# MicroLipoV1_1.net
KiCad netlist of a schematic drawn in EAGLE
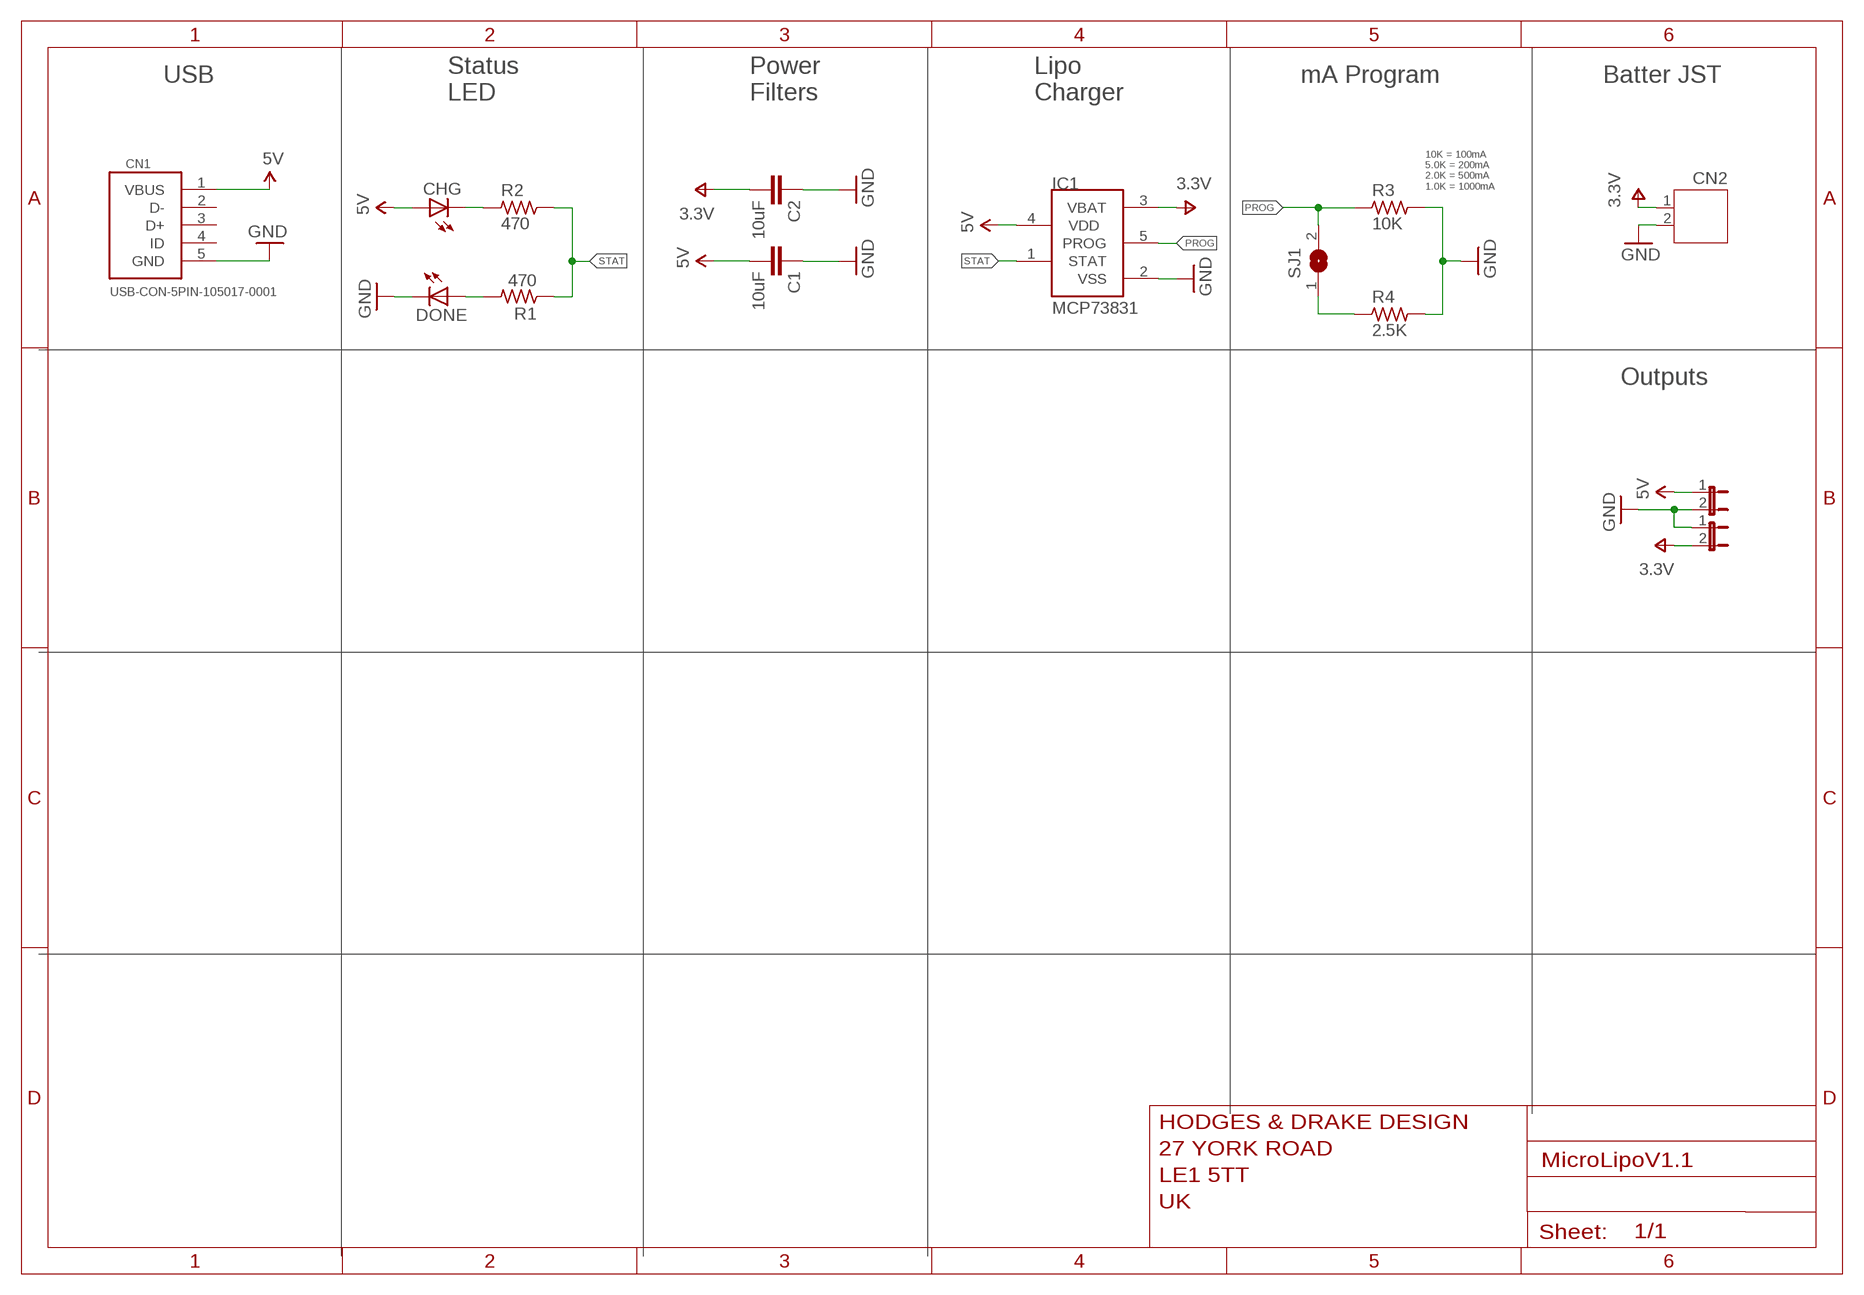
[diagram p0: schematic, sheet 1]

(export (version "E")
  (design (tool "Eeschema 10.0.6"))
  (components
    (comp (ref "C1")
      (value "10uF")
      (footprint "eagle-import:C0805K")
      (libsource (lib "eagle-import") (part "C-EUC0805K"))
    )
    (comp (ref "C2")
      (value "10uF")
      (footprint "eagle-import:C0805K")
      (libsource (lib "eagle-import") (part "C-EUC0805K"))
    )
    (comp (ref "CHG")
      (value "LEDCHIPLED_0805")
      (footprint "eagle-import:CHIPLED_0805")
      (libsource (lib "eagle-import") (part "LEDCHIPLED_0805"))
    )
    (comp (ref "CN1")
      (value "USB-CON-5PIN-105017-0001")
      (footprint "eagle-import:USB-MICRO-MOLEX-105017-0001")
      (libsource (lib "eagle-import") (part "USB-CON-5PIN-105017-0001"))
    )
    (comp (ref "CN2")
      (value "JST-PH2")
      (footprint "eagle-import:JST-PH2-S2B")
      (libsource (lib "eagle-import") (part "JST-PH2"))
    )
    (comp (ref "DONE")
      (value "LEDCHIPLED_0805")
      (footprint "eagle-import:CHIPLED_0805")
      (libsource (lib "eagle-import") (part "LEDCHIPLED_0805"))
    )
    (comp (ref "IC1")
      (value "MCP73831")
      (footprint "eagle-import:SOT23-5L")
      (libsource (lib "eagle-import") (part "MCP73831"))
    )
    (comp (ref "JP2")
      (value "JUMPER-2PTH")
      (footprint "eagle-import:1X02")
      (libsource (lib "eagle-import") (part "JUMPER-2PTH"))
    )
    (comp (ref "JP3")
      (value "JUMPER-2PTH")
      (footprint "eagle-import:1X02")
      (libsource (lib "eagle-import") (part "JUMPER-2PTH"))
    )
    (comp (ref "R1")
      (value "470")
      (footprint "eagle-import:R0805")
      (libsource (lib "eagle-import") (part "R_0805"))
    )
    (comp (ref "R2")
      (value "470")
      (footprint "eagle-import:R0805")
      (libsource (lib "eagle-import") (part "R_0805"))
    )
    (comp (ref "R3")
      (value "10K")
      (footprint "eagle-import:R0805")
      (libsource (lib "eagle-import") (part "R_0805"))
    )
    (comp (ref "R4")
      (value "2.5K")
      (footprint "eagle-import:R0805")
      (libsource (lib "eagle-import") (part "R_0805"))
    )
    (comp (ref "SJ1") (value "SJ") (footprint "eagle-import:SJ") (libsource (lib "eagle-import") (part "SJ")))
  )
  (nets
    (net (code "1") (name "3.3V") (class "Default")
      (node (ref "C2") (pin "2") (pinfunction "2_2") (pintype "passive"))
      (node (ref "CN2") (pin "1") (pinfunction "1_1") (pintype "passive"))
      (node (ref "IC1") (pin "3") (pinfunction "VBAT_3") (pintype "bidirectional"))
      (node (ref "JP3") (pin "2") (pinfunction "2_2") (pintype "passive"))
    )
    (net (code "2") (name "5V") (class "Default")
      (node (ref "C1") (pin "2") (pinfunction "2_2") (pintype "passive"))
      (node (ref "CHG") (pin "A") (pinfunction "A_A") (pintype "passive"))
      (node (ref "CN1") (pin "1") (pinfunction "VBUS_1") (pintype "power_in"))
      (node (ref "IC1") (pin "4") (pinfunction "VDD_4") (pintype "bidirectional"))
      (node (ref "JP2") (pin "1") (pinfunction "1_1") (pintype "passive"))
    )
    (net (code "3") (name "GND") (class "Default")
      (node (ref "C1") (pin "1") (pinfunction "1_1") (pintype "passive"))
      (node (ref "C2") (pin "1") (pinfunction "1_1") (pintype "passive"))
      (node (ref "CN1") (pin "5") (pinfunction "GND_5") (pintype "power_in"))
      (node (ref "CN2") (pin "2") (pinfunction "2_2") (pintype "passive"))
      (node (ref "DONE") (pin "C") (pinfunction "C_C") (pintype "passive"))
      (node (ref "IC1") (pin "2") (pinfunction "VSS_2") (pintype "bidirectional"))
      (node (ref "JP2") (pin "2") (pinfunction "2_2") (pintype "passive"))
      (node (ref "JP3") (pin "1") (pinfunction "1_1") (pintype "passive"))
      (node (ref "R3") (pin "2") (pinfunction "2_2") (pintype "passive"))
      (node (ref "R4") (pin "2") (pinfunction "2_2") (pintype "passive"))
    )
    (net (code "4") (name "Net-(CHG-PadC)") (class "Default")
      (node (ref "CHG") (pin "C") (pinfunction "C_C") (pintype "passive"))
      (node (ref "R2") (pin "1") (pinfunction "1_1") (pintype "passive"))
    )
    (net (code "5") (name "Net-(DONE-PadA)") (class "Default")
      (node (ref "DONE") (pin "A") (pinfunction "A_A") (pintype "passive"))
      (node (ref "R1") (pin "2") (pinfunction "2_2") (pintype "passive"))
    )
    (net (code "6") (name "Net-(R4-Pad1)") (class "Default")
      (node (ref "R4") (pin "1") (pinfunction "1_1") (pintype "passive"))
      (node (ref "SJ1") (pin "1") (pinfunction "1_1") (pintype "passive"))
    )
    (net (code "7") (name "PROG") (class "Default")
      (node (ref "IC1") (pin "5") (pinfunction "PROG_5") (pintype "bidirectional"))
      (node (ref "R3") (pin "1") (pinfunction "1_1") (pintype "passive"))
      (node (ref "SJ1") (pin "2") (pinfunction "2_2") (pintype "passive"))
    )
    (net (code "8") (name "STAT") (class "Default")
      (node (ref "IC1") (pin "1") (pinfunction "STAT_1") (pintype "bidirectional"))
      (node (ref "R1") (pin "1") (pinfunction "1_1") (pintype "passive"))
      (node (ref "R2") (pin "2") (pinfunction "2_2") (pintype "passive"))
    )
    (net (code "9") (name "unconnected-(CN1-D+-Pad3)") (class "Default")
      (node (ref "CN1") (pin "3") (pinfunction "D+_3") (pintype "bidirectional"))
    )
    (net (code "10") (name "unconnected-(CN1-D--Pad2)") (class "Default")
      (node (ref "CN1") (pin "2") (pinfunction "D-_2") (pintype "bidirectional"))
    )
    (net (code "11") (name "unconnected-(CN1-ID-Pad4)") (class "Default")
      (node (ref "CN1") (pin "4") (pinfunction "ID_4") (pintype "bidirectional"))
    )
  )
)
